# Switch.net
KiCad netlist of a schematic drawn in Altium Designer
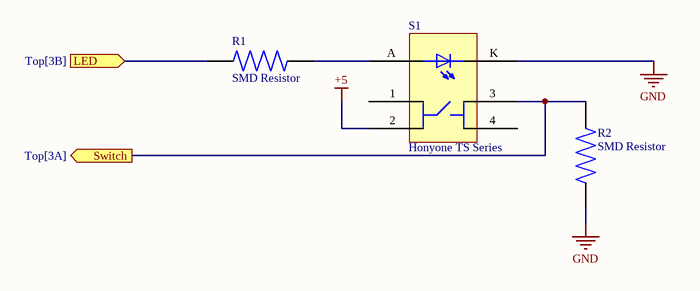
[diagram p0: Switch.SchDoc]

(export (version "E")
  (design (tool "Eeschema 10.0.6"))
  (components
    (comp (ref "R1")
      (value "SMD Resistor")
      (footprint "SMD Resistor")
      (libsource (lib "OST") (part "SMD Resistor"))
    )
    (comp (ref "R2")
      (value "SMD Resistor")
      (footprint "SMD Resistor")
      (libsource (lib "OST") (part "SMD Resistor"))
    )
    (comp (ref "S1")
      (value "Honyone TS Series")
      (footprint "Honyone TS Series")
      (libsource (lib "OST") (part "Honyone TS Series"))
    )
  )
  (nets
    (net (code "1") (name "+5") (class "Default")
      (node (ref "S1") (pin "2") (pinfunction "2_2") (pintype "passive"))
    )
    (net (code "2") (name "/LED") (class "Default")
      (node (ref "R1") (pin "1") (pinfunction "1_1") (pintype "passive"))
    )
    (net (code "3") (name "/Switch") (class "Default")
      (node (ref "R2") (pin "1") (pinfunction "1_1") (pintype "passive"))
      (node (ref "S1") (pin "3") (pinfunction "3_3") (pintype "passive"))
    )
    (net (code "4") (name "GND") (class "Default")
      (node (ref "R2") (pin "2") (pinfunction "2_2") (pintype "passive"))
      (node (ref "S1") (pin "K") (pinfunction "K_K") (pintype "passive"))
    )
    (net (code "5") (name "Net-(R1-Pad2)") (class "Default")
      (node (ref "R1") (pin "2") (pinfunction "2_2") (pintype "passive"))
      (node (ref "S1") (pin "A") (pinfunction "A_A") (pintype "passive"))
    )
    (net (code "6") (name "unconnected-(S1-Pad1)") (class "Default")
      (node (ref "S1") (pin "1") (pinfunction "1_1") (pintype "passive"))
    )
    (net (code "7") (name "unconnected-(S1-Pad4)") (class "Default")
      (node (ref "S1") (pin "4") (pinfunction "4_4") (pintype "passive"))
    )
  )
)
